# secondary_DIO.net
KiCad netlist of a schematic drawn in Altium Designer
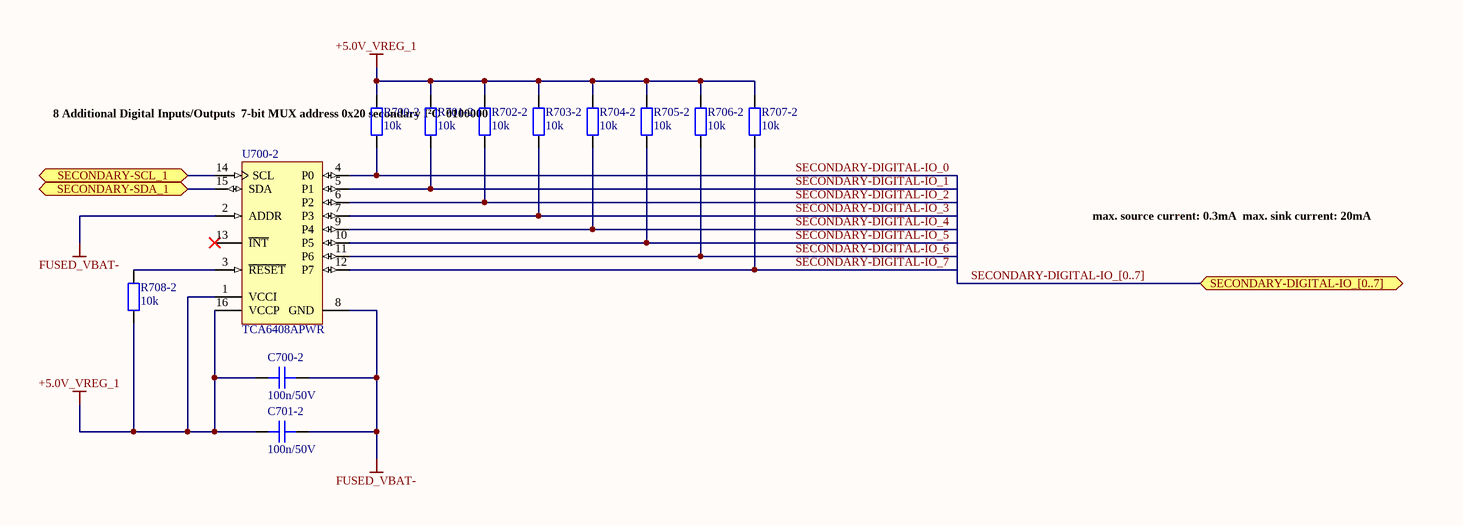
[diagram p0: secondary_DIO.SchDoc]

(export (version "E")
  (design (tool "Eeschema 10.0.6"))
  (components
    (comp (ref "C700-2")
      (value "100n/50V")
      (footprint "CAPC1608X08N")
      (description "MLCC")
      (fields (field (name "PART NUMBER") "gen_C_ceramic_100n_50V_X7R_0603"))
      (libsource (lib "OE750") (part "C"))
    )
    (comp (ref "C701-2")
      (value "100n/50V")
      (footprint "CAPC1608X08N")
      (description "MLCC")
      (fields (field (name "PART NUMBER") "gen_C_ceramic_100n_50V_X7R_0603"))
      (libsource (lib "OE750") (part "C"))
    )
    (comp (ref "R700-2")
      (value "10k")
      (footprint "RESC1608X05N")
      (description "SMD Resistor 10k 0603")
      (fields (field (name "PART NUMBER") "gen_R_10k_0603") (field (name "TOLERANCE") "1%"))
      (libsource (lib "OE750") (part "R"))
    )
    (comp (ref "R701-2")
      (value "10k")
      (footprint "RESC1608X05N")
      (description "SMD Resistor 10k 0603")
      (fields (field (name "PART NUMBER") "gen_R_10k_0603") (field (name "TOLERANCE") "1%"))
      (libsource (lib "OE750") (part "R"))
    )
    (comp (ref "R702-2")
      (value "10k")
      (footprint "RESC1608X05N")
      (description "SMD Resistor 10k 0603")
      (fields (field (name "PART NUMBER") "gen_R_10k_0603") (field (name "TOLERANCE") "1%"))
      (libsource (lib "OE750") (part "R"))
    )
    (comp (ref "R703-2")
      (value "10k")
      (footprint "RESC1608X05N")
      (description "SMD Resistor 10k 0603")
      (fields (field (name "PART NUMBER") "gen_R_10k_0603") (field (name "TOLERANCE") "1%"))
      (libsource (lib "OE750") (part "R"))
    )
    (comp (ref "R704-2")
      (value "10k")
      (footprint "RESC1608X05N")
      (description "SMD Resistor 10k 0603")
      (fields (field (name "PART NUMBER") "gen_R_10k_0603") (field (name "TOLERANCE") "1%"))
      (libsource (lib "OE750") (part "R"))
    )
    (comp (ref "R705-2")
      (value "10k")
      (footprint "RESC1608X05N")
      (description "SMD Resistor 10k 0603")
      (fields (field (name "PART NUMBER") "gen_R_10k_0603") (field (name "TOLERANCE") "1%"))
      (libsource (lib "OE750") (part "R"))
    )
    (comp (ref "R706-2")
      (value "10k")
      (footprint "RESC1608X05N")
      (description "SMD Resistor 10k 0603")
      (fields (field (name "PART NUMBER") "gen_R_10k_0603") (field (name "TOLERANCE") "1%"))
      (libsource (lib "OE750") (part "R"))
    )
    (comp (ref "R707-2")
      (value "10k")
      (footprint "RESC1608X05N")
      (description "SMD Resistor 10k 0603")
      (fields (field (name "PART NUMBER") "gen_R_10k_0603") (field (name "TOLERANCE") "1%"))
      (libsource (lib "OE750") (part "R"))
    )
    (comp (ref "R708-2")
      (value "10k")
      (footprint "RESC1608X05N")
      (description "SMD Resistor 10k 0603")
      (fields (field (name "PART NUMBER") "gen_R_10k_0603") (field (name "TOLERANCE") "1%"))
      (libsource (lib "OE750") (part "R"))
    )
    (comp (ref "U700-2")
      (value "TCA6408APWR")
      (footprint "PW0016A_L")
      (fields (field (name "MANUFACTURER") "Texas Instruments"))
      (libsource (lib "Altium Content Vault") (part "TI-TCA6408A-TSSOP_PW-16"))
    )
  )
  (nets
    (net (code "1") (name "+5.0V_VREG_1") (class "Default")
      (node (ref "C700-2") (pin "2") (pinfunction "2_2") (pintype "passive"))
      (node (ref "C701-2") (pin "2") (pinfunction "2_2") (pintype "passive"))
      (node (ref "R700-2") (pin "2") (pinfunction "2_2") (pintype "passive"))
      (node (ref "R701-2") (pin "2") (pinfunction "2_2") (pintype "passive"))
      (node (ref "R702-2") (pin "2") (pinfunction "2_2") (pintype "passive"))
      (node (ref "R703-2") (pin "2") (pinfunction "2_2") (pintype "passive"))
      (node (ref "R704-2") (pin "2") (pinfunction "2_2") (pintype "passive"))
      (node (ref "R705-2") (pin "2") (pinfunction "2_2") (pintype "passive"))
      (node (ref "R706-2") (pin "2") (pinfunction "2_2") (pintype "passive"))
      (node (ref "R707-2") (pin "2") (pinfunction "2_2") (pintype "passive"))
      (node (ref "R708-2") (pin "1") (pinfunction "1_1") (pintype "passive"))
      (node (ref "U700-2") (pin "1") (pinfunction "VCCI_1") (pintype "power_in"))
      (node (ref "U700-2") (pin "16") (pinfunction "VCCP_16") (pintype "power_in"))
    )
    (net (code "2") (name "/SECONDARY-DIGITAL-IO_0") (class "Default")
      (node (ref "R700-2") (pin "1") (pinfunction "1_1") (pintype "passive"))
      (node (ref "U700-2") (pin "4") (pinfunction "P0_4") (pintype "bidirectional"))
    )
    (net (code "3") (name "/SECONDARY-DIGITAL-IO_1") (class "Default")
      (node (ref "R701-2") (pin "1") (pinfunction "1_1") (pintype "passive"))
      (node (ref "U700-2") (pin "5") (pinfunction "P1_5") (pintype "bidirectional"))
    )
    (net (code "4") (name "/SECONDARY-DIGITAL-IO_2") (class "Default")
      (node (ref "R702-2") (pin "1") (pinfunction "1_1") (pintype "passive"))
      (node (ref "U700-2") (pin "6") (pinfunction "P2_6") (pintype "bidirectional"))
    )
    (net (code "5") (name "/SECONDARY-DIGITAL-IO_3") (class "Default")
      (node (ref "R703-2") (pin "1") (pinfunction "1_1") (pintype "passive"))
      (node (ref "U700-2") (pin "7") (pinfunction "P3_7") (pintype "bidirectional"))
    )
    (net (code "6") (name "/SECONDARY-DIGITAL-IO_4") (class "Default")
      (node (ref "R704-2") (pin "1") (pinfunction "1_1") (pintype "passive"))
      (node (ref "U700-2") (pin "9") (pinfunction "P4_9") (pintype "bidirectional"))
    )
    (net (code "7") (name "/SECONDARY-DIGITAL-IO_5") (class "Default")
      (node (ref "R705-2") (pin "1") (pinfunction "1_1") (pintype "passive"))
      (node (ref "U700-2") (pin "10") (pinfunction "P5_10") (pintype "bidirectional"))
    )
    (net (code "8") (name "/SECONDARY-DIGITAL-IO_6") (class "Default")
      (node (ref "R706-2") (pin "1") (pinfunction "1_1") (pintype "passive"))
      (node (ref "U700-2") (pin "11") (pinfunction "P6_11") (pintype "bidirectional"))
    )
    (net (code "9") (name "/SECONDARY-DIGITAL-IO_7") (class "Default")
      (node (ref "R707-2") (pin "1") (pinfunction "1_1") (pintype "passive"))
      (node (ref "U700-2") (pin "12") (pinfunction "P7_12") (pintype "bidirectional"))
    )
    (net (code "11") (name "/SECONDARY-SCL_1") (class "Default")
      (node (ref "U700-2") (pin "14") (pinfunction "SCL_14") (pintype "input"))
    )
    (net (code "12") (name "/SECONDARY-SDA_1") (class "Default")
      (node (ref "U700-2") (pin "15") (pinfunction "SDA_15") (pintype "bidirectional"))
    )
    (net (code "13") (name "FUSED_VBAT-") (class "Default")
      (node (ref "C700-2") (pin "1") (pinfunction "1_1") (pintype "passive"))
      (node (ref "C701-2") (pin "1") (pinfunction "1_1") (pintype "passive"))
      (node (ref "U700-2") (pin "2") (pinfunction "ADDR_2") (pintype "input"))
      (node (ref "U700-2") (pin "8") (pinfunction "GND_8") (pintype "power_in"))
    )
    (net (code "14") (name "Net-(U700-2-~{RESET})") (class "Default")
      (node (ref "R708-2") (pin "2") (pinfunction "2_2") (pintype "passive"))
      (node (ref "U700-2") (pin "3") (pinfunction "~{RESET}_3") (pintype "input"))
    )
    (net (code "15") (name "unconnected-(U700-2-~{INT}-Pad13)") (class "Default")
      (node (ref "U700-2") (pin "13") (pinfunction "~{INT}_13") (pintype "open_collector+no_connect"))
    )
  )
)
